# Arduino_Watering_System_V1_00.net
KiCad netlist of a schematic drawn in EAGLE
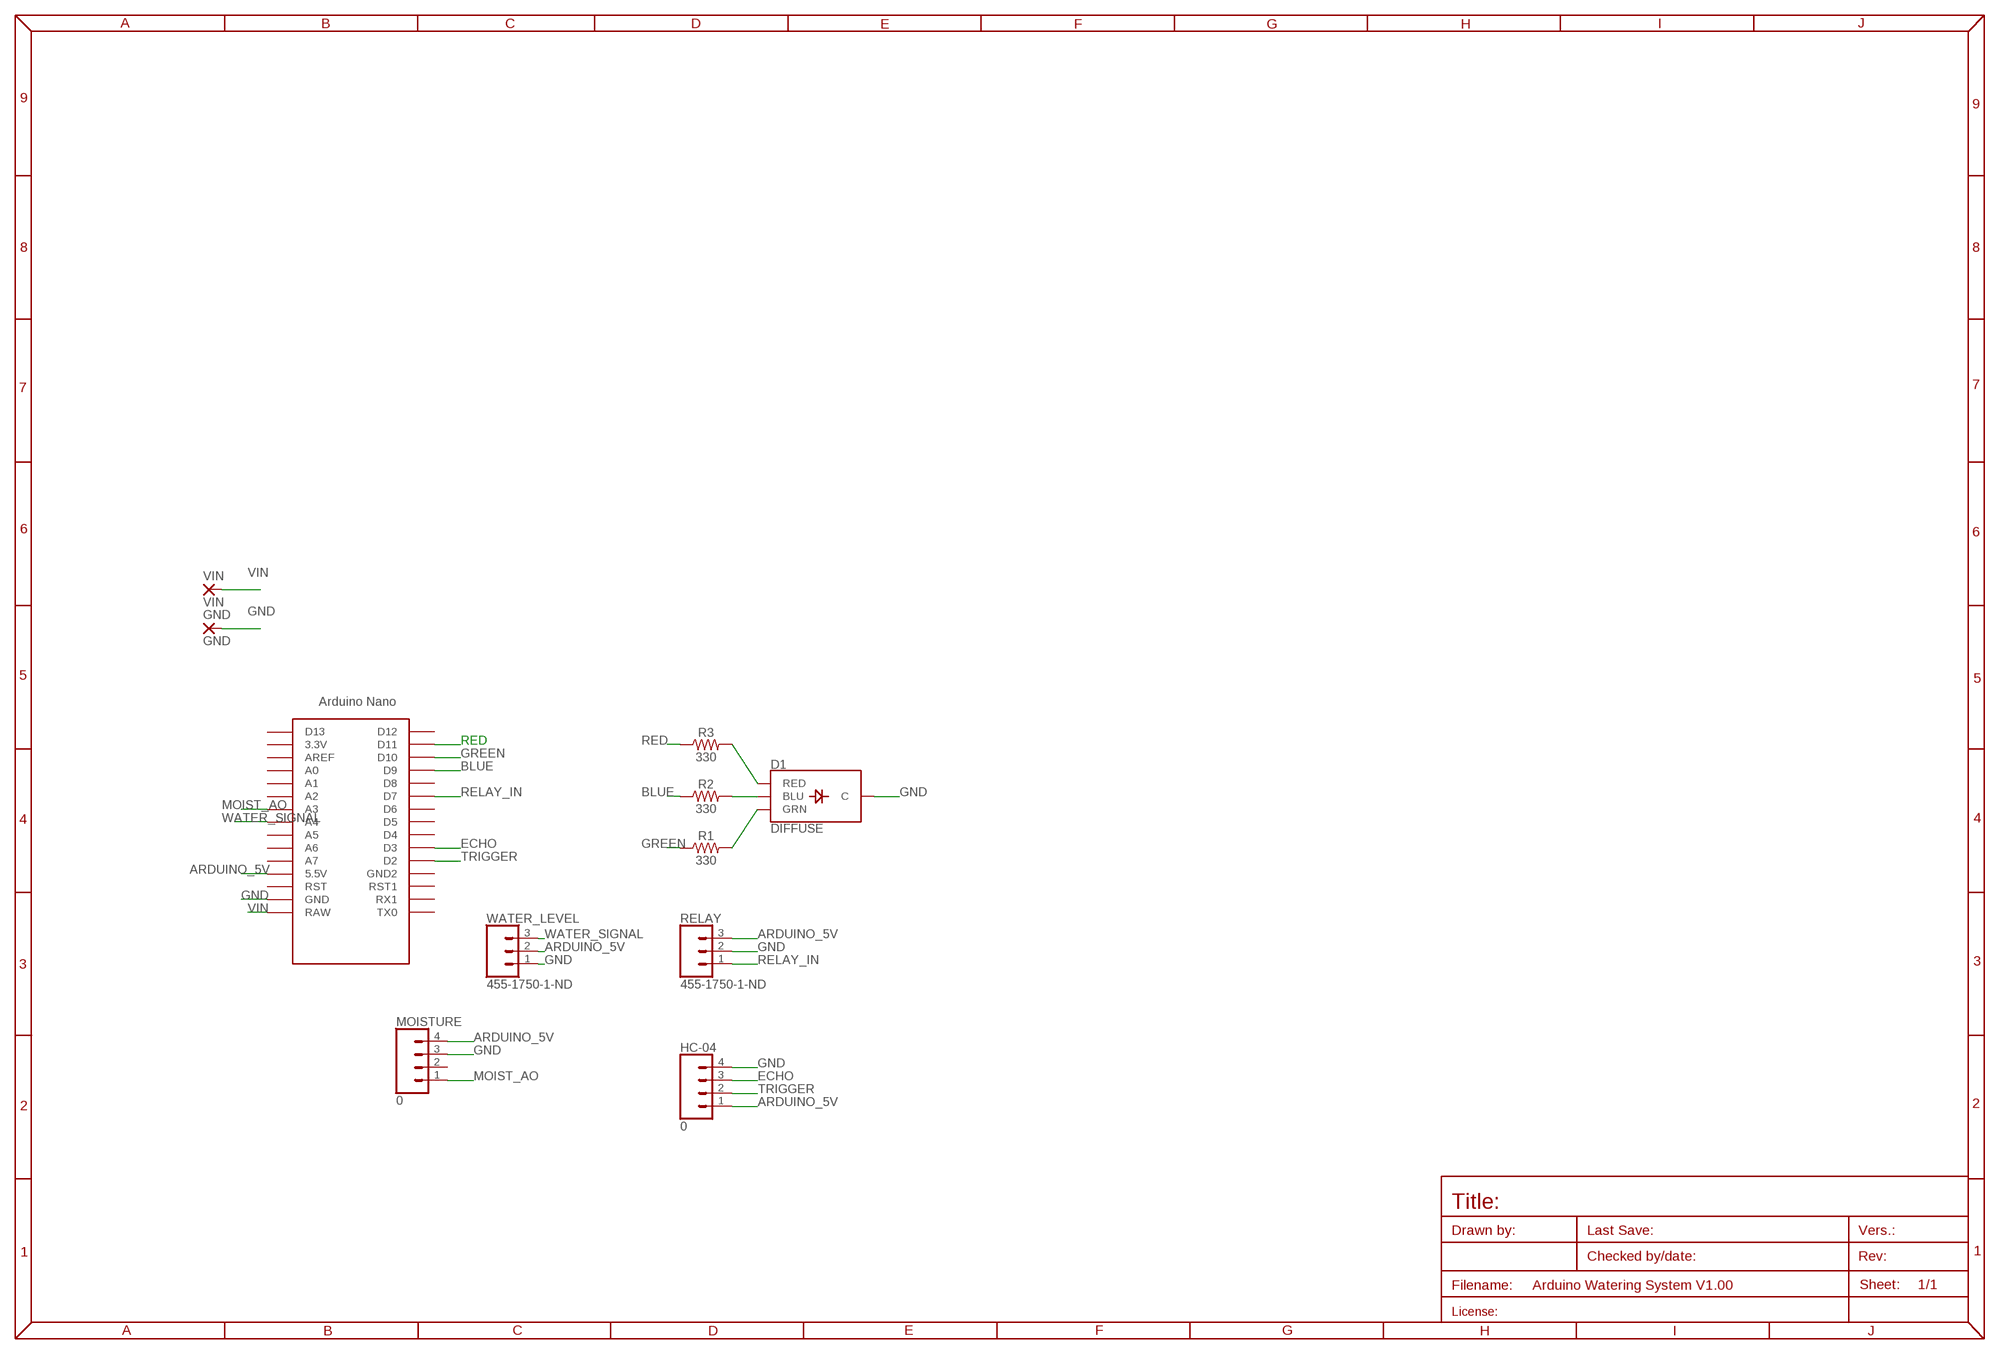
[diagram p0: schematic, sheet 1]

(export (version "E")
  (design (tool "Eeschema 10.0.6"))
  (components
    (comp (ref "D1")
      (value "DIFFUSE")
      (footprint "eagle-import:LED-RGB-THRU")
      (libsource (lib "eagle-import") (part "LED-RGB-CCDIFFUSE"))
    )
    (comp (ref "GND")
      (value "GND")
      (footprint "eagle-import:SMD2,54-5,08")
      (libsource (lib "eagle-import") (part "SMD5"))
    )
    (comp (ref "HC-04")
      (value "0")
      (footprint "eagle-import:1X04")
      (libsource (lib "eagle-import") (part "CONN_04"))
    )
    (comp (ref "MOISTURE")
      (value "0")
      (footprint "eagle-import:1X04")
      (libsource (lib "eagle-import") (part "CONN_04"))
    )
    (comp (ref "R1")
      (value "330")
      (footprint "eagle-import:AXIAL-0.3")
      (libsource (lib "eagle-import") (part "330OHM-HORIZ-1/10W-5%"))
    )
    (comp (ref "R2")
      (value "330")
      (footprint "eagle-import:AXIAL-0.3")
      (libsource (lib "eagle-import") (part "330OHM-HORIZ-1/10W-5%"))
    )
    (comp (ref "R3")
      (value "330")
      (footprint "eagle-import:AXIAL-0.3")
      (libsource (lib "eagle-import") (part "330OHM-HORIZ-1/10W-5%"))
    )
    (comp (ref "RELAY")
      (value "455-1750-1-ND")
      (footprint "eagle-import:1X03")
      (libsource (lib "eagle-import") (part "CONN_03"))
    )
    (comp (ref "U$1")
      (value "NANO")
      (footprint "eagle-import:NANO")
      (libsource (lib "eagle-import") (part "NANO"))
    )
    (comp (ref "VIN")
      (value "VIN")
      (footprint "eagle-import:SMD2,54-5,08")
      (libsource (lib "eagle-import") (part "SMD5"))
    )
    (comp (ref "WATER_LEVEL")
      (value "455-1750-1-ND")
      (footprint "eagle-import:1X03")
      (libsource (lib "eagle-import") (part "CONN_03"))
    )
  )
  (nets
    (net (code "1") (name "/ARDUINO_5V") (class "Default")
      (node (ref "HC-04") (pin "1") (pinfunction "1_1") (pintype "passive"))
      (node (ref "MOISTURE") (pin "4") (pinfunction "4_4") (pintype "passive"))
      (node (ref "RELAY") (pin "3") (pinfunction "3_3") (pintype "passive"))
      (node (ref "U$1") (pin "5V") (pinfunction "5.5V_5V") (pintype "bidirectional"))
      (node (ref "WATER_LEVEL") (pin "2") (pinfunction "2_2") (pintype "passive"))
    )
    (net (code "2") (name "/BLUE") (class "Default")
      (node (ref "R2") (pin "P$1") (pinfunction "1_P$1") (pintype "passive"))
      (node (ref "U$1") (pin "D9") (pinfunction "D9_D9") (pintype "bidirectional"))
    )
    (net (code "3") (name "/ECHO") (class "Default")
      (node (ref "HC-04") (pin "3") (pinfunction "3_3") (pintype "passive"))
      (node (ref "U$1") (pin "D3") (pinfunction "D3_D3") (pintype "bidirectional"))
    )
    (net (code "4") (name "/GND") (class "Default")
      (node (ref "D1") (pin "2") (pinfunction "C_2") (pintype "bidirectional"))
      (node (ref "GND") (pin "1") (pinfunction "P_1") (pintype "passive"))
      (node (ref "HC-04") (pin "4") (pinfunction "4_4") (pintype "passive"))
      (node (ref "MOISTURE") (pin "3") (pinfunction "3_3") (pintype "passive"))
      (node (ref "RELAY") (pin "2") (pinfunction "2_2") (pintype "passive"))
      (node (ref "U$1") (pin "GND") (pinfunction "GND_GND") (pintype "bidirectional"))
      (node (ref "WATER_LEVEL") (pin "1") (pinfunction "1_1") (pintype "passive"))
    )
    (net (code "5") (name "/GREEN") (class "Default")
      (node (ref "R1") (pin "P$1") (pinfunction "1_P$1") (pintype "passive"))
      (node (ref "U$1") (pin "D10") (pinfunction "D10_D10") (pintype "bidirectional"))
    )
    (net (code "6") (name "/MOIST_AO") (class "Default")
      (node (ref "MOISTURE") (pin "1") (pinfunction "1_1") (pintype "passive"))
      (node (ref "U$1") (pin "A3") (pinfunction "A3_A3") (pintype "bidirectional"))
    )
    (net (code "7") (name "/RED") (class "Default")
      (node (ref "R3") (pin "P$1") (pinfunction "1_P$1") (pintype "passive"))
      (node (ref "U$1") (pin "D11") (pinfunction "D11_D11") (pintype "bidirectional"))
    )
    (net (code "8") (name "/RELAY_IN") (class "Default")
      (node (ref "RELAY") (pin "1") (pinfunction "1_1") (pintype "passive"))
      (node (ref "U$1") (pin "D7") (pinfunction "D7_D7") (pintype "bidirectional"))
    )
    (net (code "9") (name "/TRIGGER") (class "Default")
      (node (ref "HC-04") (pin "2") (pinfunction "2_2") (pintype "passive"))
      (node (ref "U$1") (pin "D2") (pinfunction "D2_D2") (pintype "bidirectional"))
    )
    (net (code "10") (name "/VIN") (class "Default")
      (node (ref "U$1") (pin "RAW") (pinfunction "RAW_RAW") (pintype "bidirectional"))
      (node (ref "VIN") (pin "1") (pinfunction "P_1") (pintype "passive"))
    )
    (net (code "11") (name "/WATER_SIGNAL") (class "Default")
      (node (ref "U$1") (pin "A4") (pinfunction "A4_A4") (pintype "bidirectional"))
      (node (ref "WATER_LEVEL") (pin "3") (pinfunction "3_3") (pintype "passive"))
    )
    (net (code "12") (name "Net-(D1-BLU)") (class "Default")
      (node (ref "D1") (pin "4") (pinfunction "BLU_4") (pintype "bidirectional"))
      (node (ref "R2") (pin "P$2") (pinfunction "2_P$2") (pintype "passive"))
    )
    (net (code "13") (name "Net-(D1-GRN)") (class "Default")
      (node (ref "D1") (pin "3") (pinfunction "GRN_3") (pintype "bidirectional"))
      (node (ref "R1") (pin "P$2") (pinfunction "2_P$2") (pintype "passive"))
    )
    (net (code "14") (name "Net-(D1-RED)") (class "Default")
      (node (ref "D1") (pin "1") (pinfunction "RED_1") (pintype "bidirectional"))
      (node (ref "R3") (pin "P$2") (pinfunction "2_P$2") (pintype "passive"))
    )
    (net (code "15") (name "unconnected-(MOISTURE-Pad2)") (class "Default")
      (node (ref "MOISTURE") (pin "2") (pinfunction "2_2") (pintype "passive"))
    )
    (net (code "16") (name "unconnected-(U$1-GND2-PadGND1)") (class "Default")
      (node (ref "U$1") (pin "GND1") (pinfunction "GND2_GND1") (pintype "bidirectional"))
    )
    (net (code "17") (name "unconnected-(U$1-Pad3.3V)") (class "Default")
      (node (ref "U$1") (pin "3.3V") (pinfunction "3.3V_3.3V") (pintype "bidirectional"))
    )
    (net (code "18") (name "unconnected-(U$1-PadA0)") (class "Default")
      (node (ref "U$1") (pin "A0") (pinfunction "A0_A0") (pintype "bidirectional"))
    )
    (net (code "19") (name "unconnected-(U$1-PadA1)") (class "Default")
      (node (ref "U$1") (pin "A1") (pinfunction "A1_A1") (pintype "bidirectional"))
    )
    (net (code "20") (name "unconnected-(U$1-PadA2)") (class "Default")
      (node (ref "U$1") (pin "A2") (pinfunction "A2_A2") (pintype "bidirectional"))
    )
    (net (code "21") (name "unconnected-(U$1-PadA5)") (class "Default")
      (node (ref "U$1") (pin "A5") (pinfunction "A5_A5") (pintype "bidirectional"))
    )
    (net (code "22") (name "unconnected-(U$1-PadA6)") (class "Default")
      (node (ref "U$1") (pin "A6") (pinfunction "A6_A6") (pintype "bidirectional"))
    )
    (net (code "23") (name "unconnected-(U$1-PadA7)") (class "Default")
      (node (ref "U$1") (pin "A7") (pinfunction "A7_A7") (pintype "bidirectional"))
    )
    (net (code "24") (name "unconnected-(U$1-PadAREF)") (class "Default")
      (node (ref "U$1") (pin "AREF") (pinfunction "AREF_AREF") (pintype "bidirectional"))
    )
    (net (code "25") (name "unconnected-(U$1-PadD4)") (class "Default")
      (node (ref "U$1") (pin "D4") (pinfunction "D4_D4") (pintype "bidirectional"))
    )
    (net (code "26") (name "unconnected-(U$1-PadD5)") (class "Default")
      (node (ref "U$1") (pin "D5") (pinfunction "D5_D5") (pintype "bidirectional"))
    )
    (net (code "27") (name "unconnected-(U$1-PadD6)") (class "Default")
      (node (ref "U$1") (pin "D6") (pinfunction "D6_D6") (pintype "bidirectional"))
    )
    (net (code "28") (name "unconnected-(U$1-PadD8)") (class "Default")
      (node (ref "U$1") (pin "D8") (pinfunction "D8_D8") (pintype "bidirectional"))
    )
    (net (code "29") (name "unconnected-(U$1-PadD12)") (class "Default")
      (node (ref "U$1") (pin "D12") (pinfunction "D12_D12") (pintype "bidirectional"))
    )
    (net (code "30") (name "unconnected-(U$1-PadD13)") (class "Default")
      (node (ref "U$1") (pin "D13") (pinfunction "D13_D13") (pintype "bidirectional"))
    )
    (net (code "31") (name "unconnected-(U$1-PadICSP1)") (class "Default")
      (node (ref "U$1") (pin "ICSP1") (pinfunction "ICSP1_ICSP1") (pintype "bidirectional"))
    )
    (net (code "32") (name "unconnected-(U$1-PadICSP2)") (class "Default")
      (node (ref "U$1") (pin "ICSP2") (pinfunction "ICSP2_ICSP2") (pintype "bidirectional"))
    )
    (net (code "33") (name "unconnected-(U$1-PadICSP3)") (class "Default")
      (node (ref "U$1") (pin "ICSP3") (pinfunction "ICSP3_ICSP3") (pintype "bidirectional"))
    )
    (net (code "34") (name "unconnected-(U$1-PadICSP4)") (class "Default")
      (node (ref "U$1") (pin "ICSP4") (pinfunction "ICSP4_ICSP4") (pintype "bidirectional"))
    )
    (net (code "35") (name "unconnected-(U$1-PadICSP5)") (class "Default")
      (node (ref "U$1") (pin "ICSP5") (pinfunction "ICSP5_ICSP5") (pintype "bidirectional"))
    )
    (net (code "36") (name "unconnected-(U$1-PadICSP6)") (class "Default")
      (node (ref "U$1") (pin "ICSP6") (pinfunction "ICSP6_ICSP6") (pintype "bidirectional"))
    )
    (net (code "37") (name "unconnected-(U$1-PadRST)") (class "Default")
      (node (ref "U$1") (pin "RST") (pinfunction "RST_RST") (pintype "bidirectional"))
    )
    (net (code "38") (name "unconnected-(U$1-PadRST1)") (class "Default")
      (node (ref "U$1") (pin "RST1") (pinfunction "RST1_RST1") (pintype "bidirectional"))
    )
    (net (code "39") (name "unconnected-(U$1-PadRX1)") (class "Default")
      (node (ref "U$1") (pin "RX1") (pinfunction "RX1_RX1") (pintype "bidirectional"))
    )
    (net (code "40") (name "unconnected-(U$1-PadTX0)") (class "Default")
      (node (ref "U$1") (pin "TX0") (pinfunction "TX0_TX0") (pintype "bidirectional"))
    )
  )
)
